# Radio.net
KiCad netlist of a schematic drawn in Altium Designer
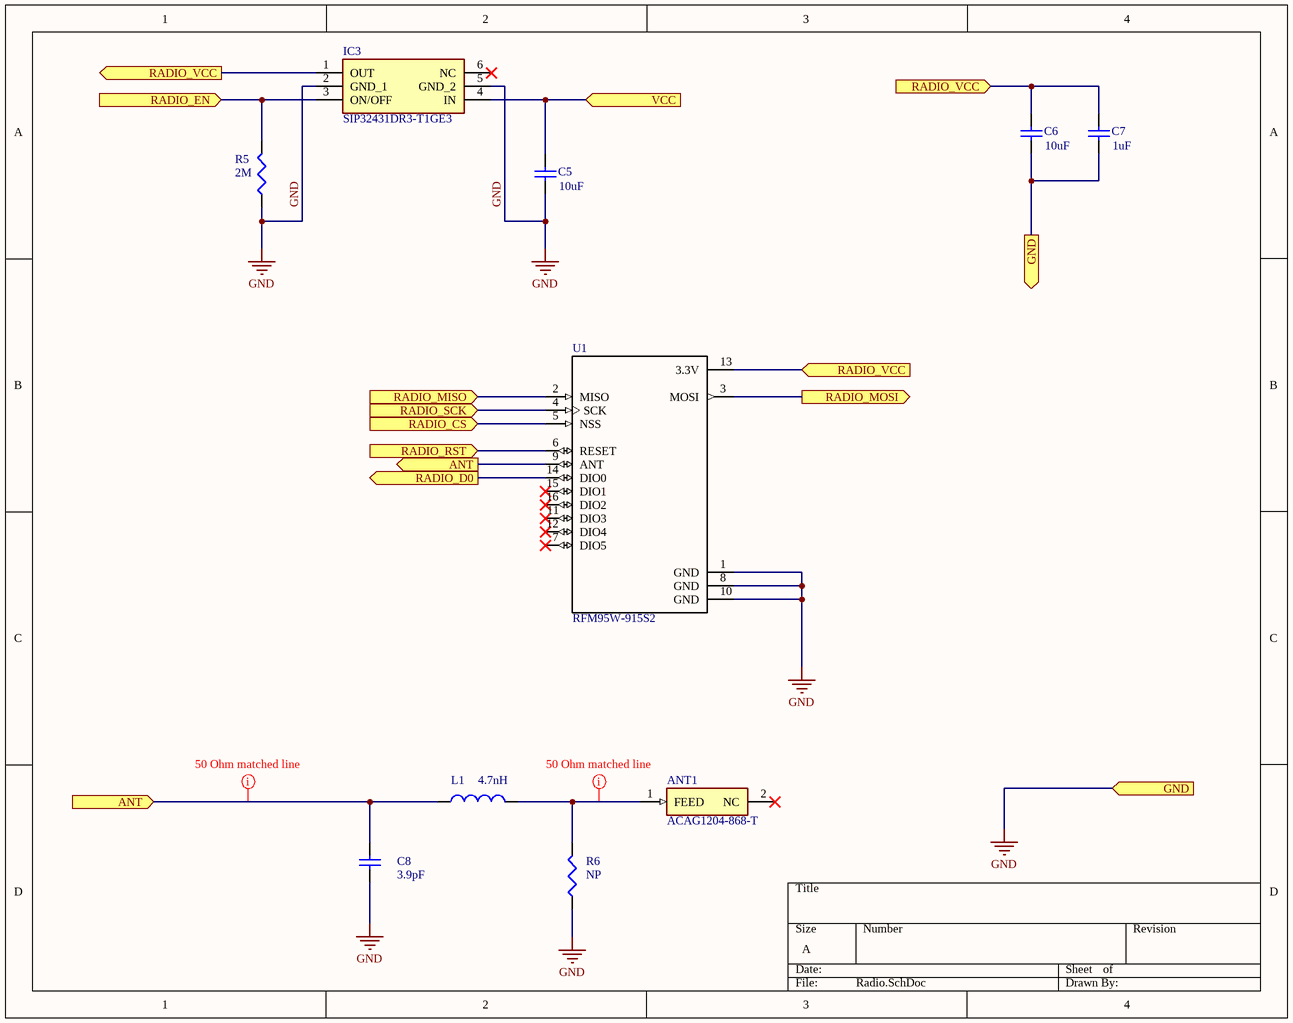
[diagram p0: Radio.SchDoc]

(export (version "E")
  (design (tool "Eeschema 10.0.6"))
  (components
    (comp (ref "ANT1")
      (value "ACAG1204-868-T")
      (footprint "ANTC12040X170N")
      (description "Antenna")
      (fields (field (name "MOUSER PART NUMBER") "815-G1204-868-T"))
      (libsource (lib "*") (part "ACAG1204-868-T"))
    )
    (comp (ref "C5")
      (value "10uF")
      (footprint "1608[0603]")
      (description "CAP CER 6.3V X5R/X7R 0603")
      (fields (field (name "Comment") "Cap") (field (name "PUBLISHER") "Altium Limited"))
      (libsource (lib "Miscellaneous Devices") (part "Cap"))
    )
    (comp (ref "C6")
      (value "10uF")
      (footprint "1608[0603]")
      (description "CAP CER 6.3V X5R/X7R 0603")
      (fields (field (name "Comment") "Cap") (field (name "PUBLISHER") "Altium Limited"))
      (libsource (lib "Miscellaneous Devices") (part "Cap"))
    )
    (comp (ref "C7")
      (value "1uF")
      (footprint "1608[0603]")
      (description "CAP CER 6.3V X5R/X7R 0603")
      (fields (field (name "Comment") "Cap") (field (name "PUBLISHER") "Altium Limited"))
      (libsource (lib "Miscellaneous Devices") (part "Cap"))
    )
    (comp (ref "C8")
      (value "3.9pF")
      (footprint "1608[0603]")
      (description "Capacitor")
      (fields (field (name "PUBLISHER") "Altium Limited"))
      (libsource (lib "Miscellaneous Devices") (part "Cap"))
    )
    (comp (ref "IC3")
      (value "SIP32431DR3-T1GE3")
      (footprint "SamacSys:SOT65P210X110-6N")
      (description "10 pA, Ultra Low Leakage and Quiescent Current,\r\nLoad Switch with Reverse Blocking")
      (fields (field (name "MOUSER PART NUMBER") "781-SIP32431DR3-GE3"))
      (libsource (lib "*") (part "SIP32431DR3-T1GE3"))
    )
    (comp (ref "L1")
      (value "4.7nH")
      (footprint "1608[0603]")
      (description "Inductor")
      (fields (field (name "PUBLISHER") "Altium Limited"))
      (libsource (lib "Miscellaneous Devices") (part "Inductor"))
    )
    (comp (ref "R5")
      (value "2M")
      (footprint "J1-0603")
      (description "RES 1/10W 1% 0603 SMD")
      (fields (field (name "Comment") "Res3") (field (name "PUBLISHER") "Altium Limited"))
      (libsource (lib "Miscellaneous Devices") (part "Res3"))
    )
    (comp (ref "R6")
      (value "NP")
      (footprint "1608[0603]")
      (description "Resistor")
      (fields (field (name "PUBLISHER") "Altium Limited"))
      (libsource (lib "Miscellaneous Devices") (part "Res3"))
    )
    (comp (ref "U1")
      (value "RFM95W-915S2")
      (footprint "RFM95W-915S2:*XCVR_RFM69HW-868S2")
      (description "RFM95W LoRA Transceiver Module 915MHz")
      (fields (field (name "MF") "RF Solutions"))
      (libsource (lib "RFM95W-915S2") (part "RFM95W-915S2"))
    )
  )
  (nets
    (net (code "1") (name "/ANT") (class "Default")
      (node (ref "C8") (pin "2") (pinfunction "2_2") (pintype "passive"))
      (node (ref "L1") (pin "1") (pinfunction "1_1") (pintype "passive"))
      (node (ref "U1") (pin "9") (pinfunction "ANT_9") (pintype "bidirectional"))
    )
    (net (code "2") (name "/RADIO_CS") (class "Default")
      (node (ref "U1") (pin "5") (pinfunction "NSS_5") (pintype "input"))
    )
    (net (code "3") (name "/RADIO_D0") (class "Default")
      (node (ref "U1") (pin "14") (pinfunction "DIO0_14") (pintype "bidirectional"))
    )
    (net (code "4") (name "/RADIO_EN") (class "Default")
      (node (ref "IC3") (pin "3") (pinfunction "ON/OFF_3") (pintype "passive"))
      (node (ref "R5") (pin "2") (pinfunction "2_2") (pintype "passive"))
    )
    (net (code "5") (name "/RADIO_MISO") (class "Default")
      (node (ref "U1") (pin "2") (pinfunction "MISO_2") (pintype "input"))
    )
    (net (code "6") (name "/RADIO_MOSI") (class "Default")
      (node (ref "U1") (pin "3") (pinfunction "MOSI_3") (pintype "output"))
    )
    (net (code "7") (name "/RADIO_RST") (class "Default")
      (node (ref "U1") (pin "6") (pinfunction "RESET_6") (pintype "bidirectional"))
    )
    (net (code "8") (name "/RADIO_SCK") (class "Default")
      (node (ref "U1") (pin "4") (pinfunction "SCK_4") (pintype "input"))
    )
    (net (code "9") (name "/RADIO_VCC") (class "Default")
      (node (ref "C6") (pin "2") (pinfunction "2_2") (pintype "passive"))
      (node (ref "C7") (pin "2") (pinfunction "2_2") (pintype "passive"))
      (node (ref "IC3") (pin "1") (pinfunction "OUT_1") (pintype "passive"))
      (node (ref "U1") (pin "13") (pinfunction "3.3V_13") (pintype "power_in"))
    )
    (net (code "10") (name "/VCC") (class "Default")
      (node (ref "C5") (pin "2") (pinfunction "2_2") (pintype "passive"))
      (node (ref "IC3") (pin "4") (pinfunction "IN_4") (pintype "passive"))
    )
    (net (code "11") (name "GND") (class "Default")
      (node (ref "C5") (pin "1") (pinfunction "1_1") (pintype "passive"))
      (node (ref "C6") (pin "1") (pinfunction "1_1") (pintype "passive"))
      (node (ref "C7") (pin "1") (pinfunction "1_1") (pintype "passive"))
      (node (ref "C8") (pin "1") (pinfunction "1_1") (pintype "passive"))
      (node (ref "IC3") (pin "2") (pinfunction "GND_1_2") (pintype "passive"))
      (node (ref "IC3") (pin "5") (pinfunction "GND_2_5") (pintype "passive"))
      (node (ref "R5") (pin "1") (pinfunction "1_1") (pintype "passive"))
      (node (ref "R6") (pin "1") (pinfunction "1_1") (pintype "passive"))
      (node (ref "U1") (pin "1") (pinfunction "GND_1") (pintype "power_in"))
      (node (ref "U1") (pin "10") (pinfunction "GND_10") (pintype "power_in"))
      (node (ref "U1") (pin "8") (pinfunction "GND_8") (pintype "power_in"))
    )
    (net (code "12") (name "Net-(ANT1-FEED)") (class "Default")
      (node (ref "ANT1") (pin "1") (pinfunction "FEED_1") (pintype "input"))
      (node (ref "L1") (pin "2") (pinfunction "2_2") (pintype "passive"))
      (node (ref "R6") (pin "2") (pinfunction "2_2") (pintype "passive"))
    )
    (net (code "13") (name "unconnected-(ANT1-NC-Pad2)") (class "Default")
      (node (ref "ANT1") (pin "2") (pinfunction "NC_2") (pintype "passive+no_connect"))
    )
    (net (code "14") (name "unconnected-(IC3-NC-Pad6)") (class "Default")
      (node (ref "IC3") (pin "6") (pinfunction "NC_6") (pintype "passive+no_connect"))
    )
    (net (code "15") (name "unconnected-(U1-DIO1-Pad15)") (class "Default")
      (node (ref "U1") (pin "15") (pinfunction "DIO1_15") (pintype "bidirectional+no_connect"))
    )
    (net (code "16") (name "unconnected-(U1-DIO2-Pad16)") (class "Default")
      (node (ref "U1") (pin "16") (pinfunction "DIO2_16") (pintype "bidirectional+no_connect"))
    )
    (net (code "17") (name "unconnected-(U1-DIO3-Pad11)") (class "Default")
      (node (ref "U1") (pin "11") (pinfunction "DIO3_11") (pintype "bidirectional+no_connect"))
    )
    (net (code "18") (name "unconnected-(U1-DIO4-Pad12)") (class "Default")
      (node (ref "U1") (pin "12") (pinfunction "DIO4_12") (pintype "bidirectional+no_connect"))
    )
    (net (code "19") (name "unconnected-(U1-DIO5-Pad7)") (class "Default")
      (node (ref "U1") (pin "7") (pinfunction "DIO5_7") (pintype "bidirectional+no_connect"))
    )
  )
)
